# LED.net
KiCad netlist of a schematic drawn in EAGLE
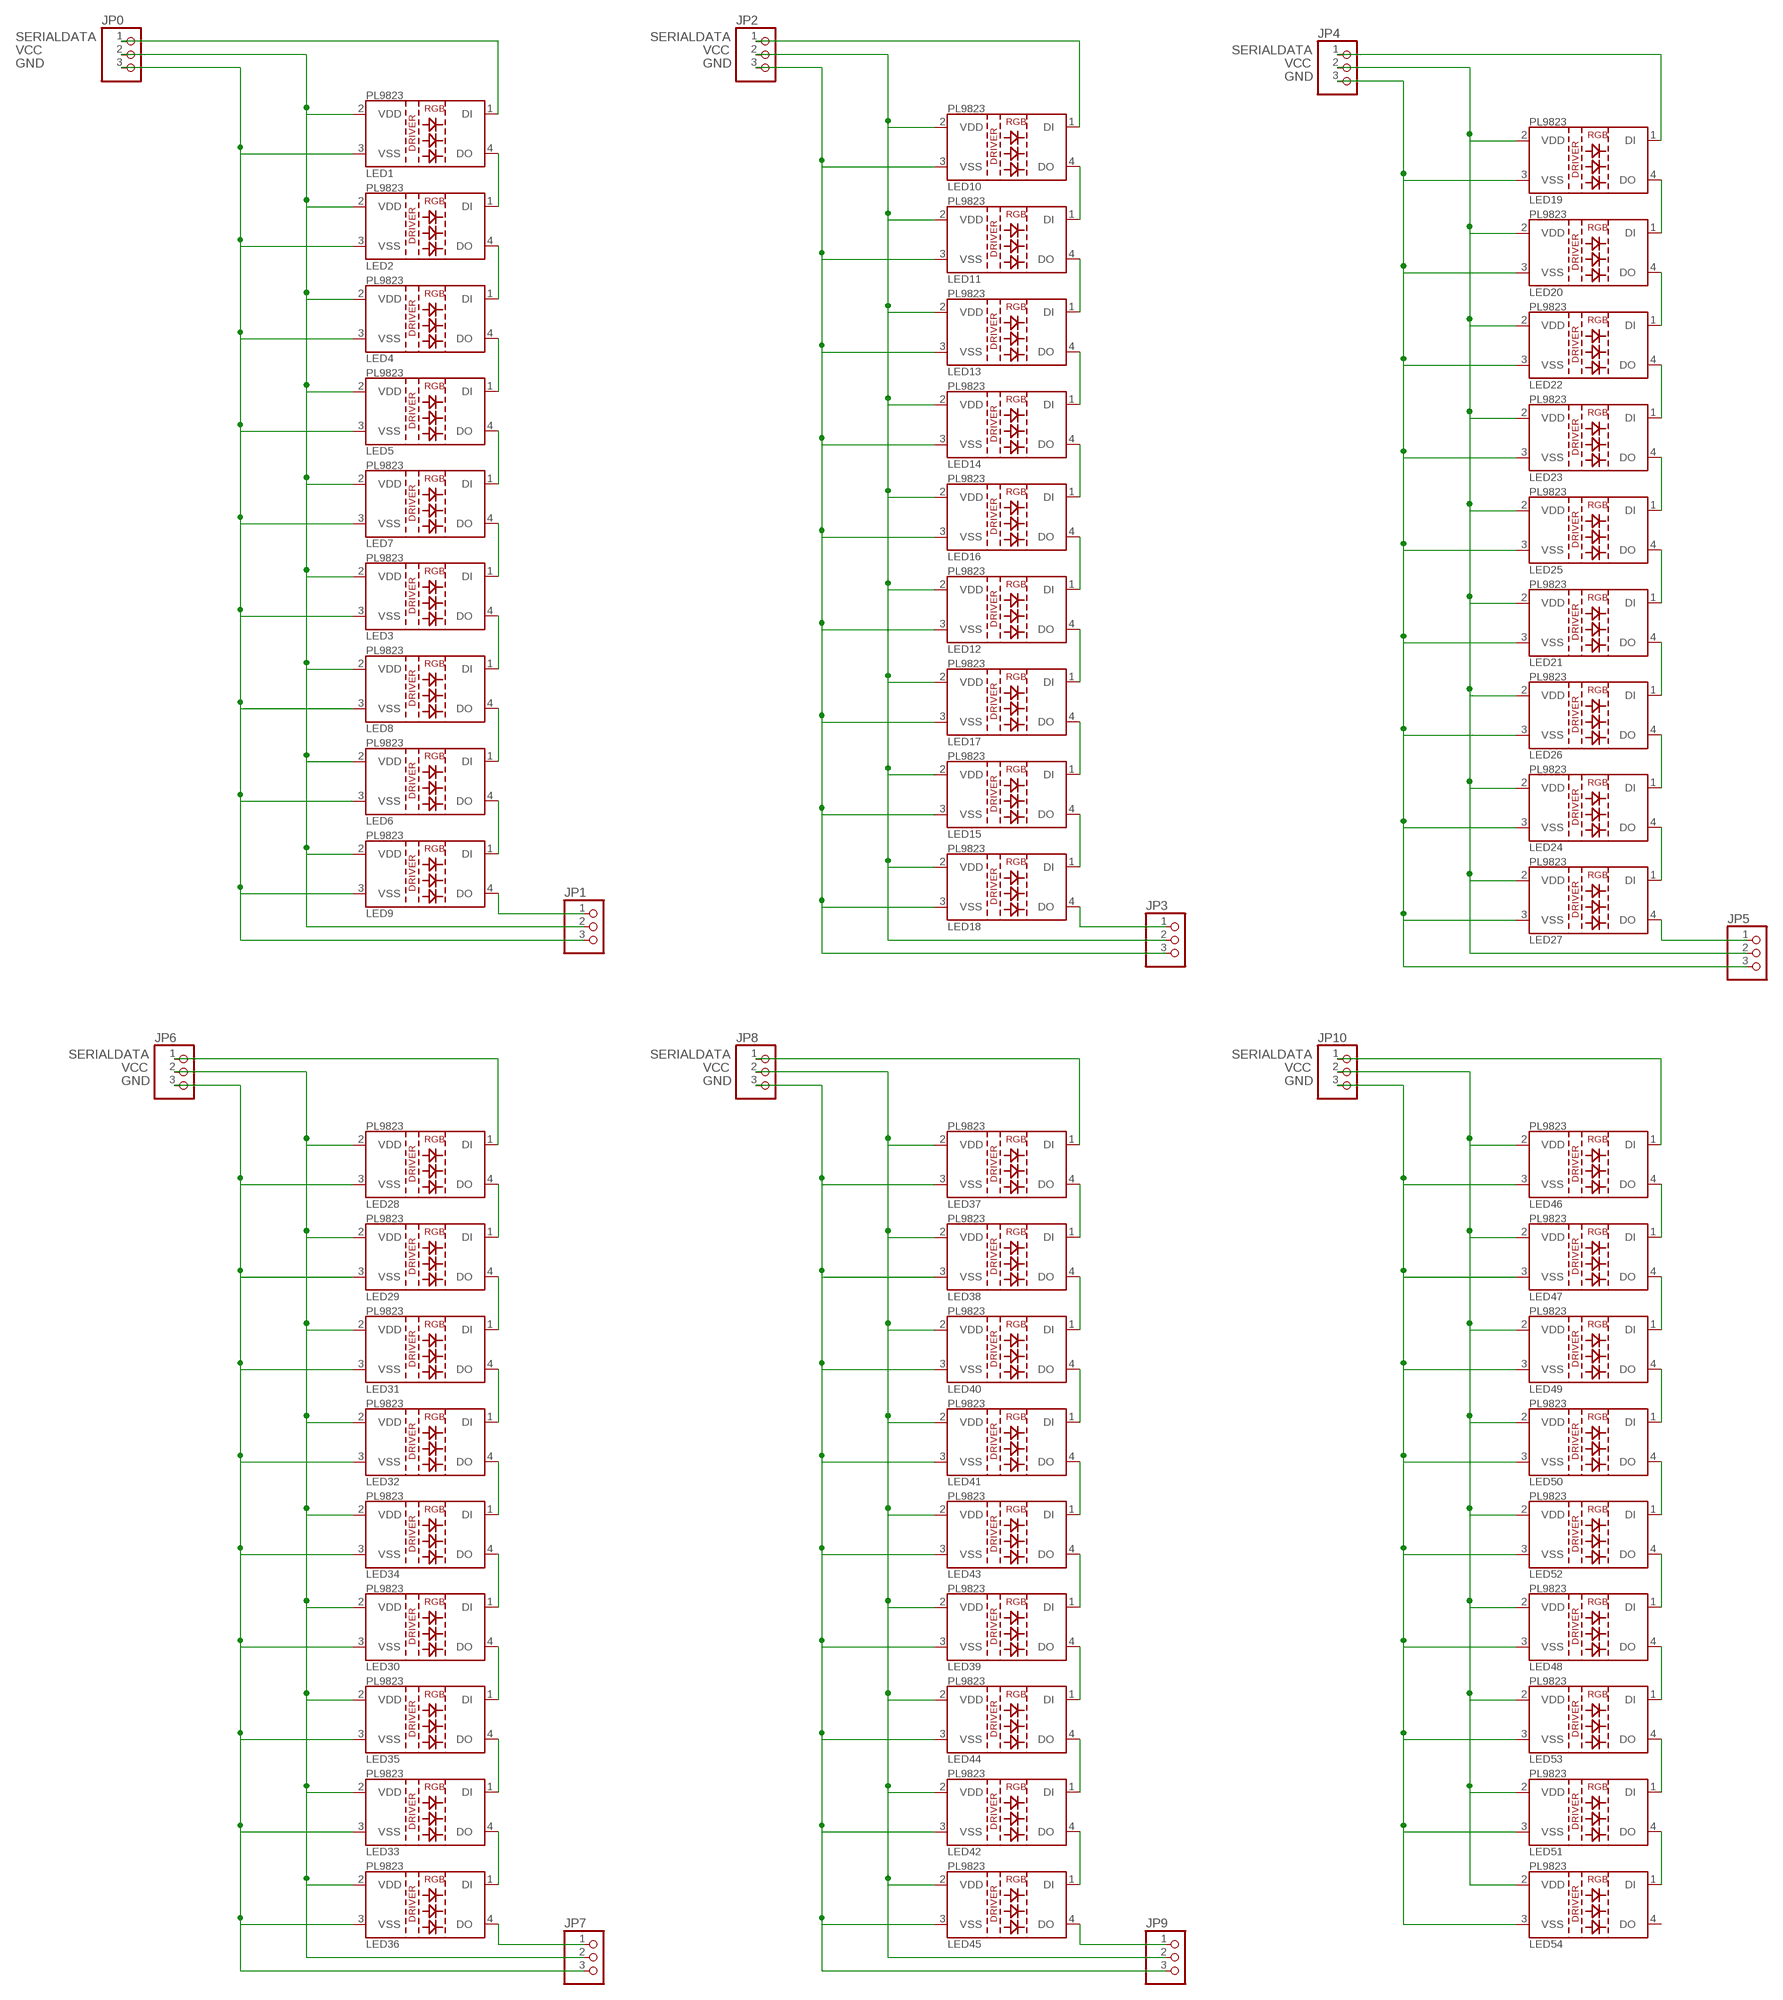
[diagram p0: schematic, sheet 1]

(export (version "E")
  (design (tool "Eeschema 10.0.6"))
  (components
    (comp (ref "JP0")
      (value "PINHD-1X3")
      (footprint "eagle-import:1X03")
      (libsource (lib "eagle-import") (part "PINHD-1X3"))
    )
    (comp (ref "JP1")
      (value "PINHD-1X3")
      (footprint "eagle-import:1X03")
      (libsource (lib "eagle-import") (part "PINHD-1X3"))
    )
    (comp (ref "JP2")
      (value "PINHD-1X3")
      (footprint "eagle-import:1X03")
      (libsource (lib "eagle-import") (part "PINHD-1X3"))
    )
    (comp (ref "JP3")
      (value "PINHD-1X3")
      (footprint "eagle-import:1X03")
      (libsource (lib "eagle-import") (part "PINHD-1X3"))
    )
    (comp (ref "JP4")
      (value "PINHD-1X3")
      (footprint "eagle-import:1X03")
      (libsource (lib "eagle-import") (part "PINHD-1X3"))
    )
    (comp (ref "JP5")
      (value "PINHD-1X3")
      (footprint "eagle-import:1X03")
      (libsource (lib "eagle-import") (part "PINHD-1X3"))
    )
    (comp (ref "JP6")
      (value "PINHD-1X3")
      (footprint "eagle-import:1X03")
      (libsource (lib "eagle-import") (part "PINHD-1X3"))
    )
    (comp (ref "JP7")
      (value "PINHD-1X3")
      (footprint "eagle-import:1X03")
      (libsource (lib "eagle-import") (part "PINHD-1X3"))
    )
    (comp (ref "JP8")
      (value "PINHD-1X3")
      (footprint "eagle-import:1X03")
      (libsource (lib "eagle-import") (part "PINHD-1X3"))
    )
    (comp (ref "JP9")
      (value "PINHD-1X3")
      (footprint "eagle-import:1X03")
      (libsource (lib "eagle-import") (part "PINHD-1X3"))
    )
    (comp (ref "JP10")
      (value "PINHD-1X3")
      (footprint "eagle-import:1X03")
      (libsource (lib "eagle-import") (part "PINHD-1X3"))
    )
    (comp (ref "LED1")
      (value "LED-PL9823-F5")
      (footprint "eagle-import:LED-PL9823-F5")
      (libsource (lib "eagle-import") (part "LED-PL9823-F5"))
    )
    (comp (ref "LED2")
      (value "LED-PL9823-F5")
      (footprint "eagle-import:LED-PL9823-F5")
      (libsource (lib "eagle-import") (part "LED-PL9823-F5"))
    )
    (comp (ref "LED3")
      (value "LED-PL9823-F5")
      (footprint "eagle-import:LED-PL9823-F5")
      (libsource (lib "eagle-import") (part "LED-PL9823-F5"))
    )
    (comp (ref "LED4")
      (value "LED-PL9823-F5")
      (footprint "eagle-import:LED-PL9823-F5")
      (libsource (lib "eagle-import") (part "LED-PL9823-F5"))
    )
    (comp (ref "LED5")
      (value "LED-PL9823-F5")
      (footprint "eagle-import:LED-PL9823-F5")
      (libsource (lib "eagle-import") (part "LED-PL9823-F5"))
    )
    (comp (ref "LED6")
      (value "LED-PL9823-F5")
      (footprint "eagle-import:LED-PL9823-F5")
      (libsource (lib "eagle-import") (part "LED-PL9823-F5"))
    )
    (comp (ref "LED7")
      (value "LED-PL9823-F5")
      (footprint "eagle-import:LED-PL9823-F5")
      (libsource (lib "eagle-import") (part "LED-PL9823-F5"))
    )
    (comp (ref "LED8")
      (value "LED-PL9823-F5")
      (footprint "eagle-import:LED-PL9823-F5")
      (libsource (lib "eagle-import") (part "LED-PL9823-F5"))
    )
    (comp (ref "LED9")
      (value "LED-PL9823-F5")
      (footprint "eagle-import:LED-PL9823-F5")
      (libsource (lib "eagle-import") (part "LED-PL9823-F5"))
    )
    (comp (ref "LED10")
      (value "LED-PL9823-F5")
      (footprint "eagle-import:LED-PL9823-F5")
      (libsource (lib "eagle-import") (part "LED-PL9823-F5"))
    )
    (comp (ref "LED11")
      (value "LED-PL9823-F5")
      (footprint "eagle-import:LED-PL9823-F5")
      (libsource (lib "eagle-import") (part "LED-PL9823-F5"))
    )
    (comp (ref "LED12")
      (value "LED-PL9823-F5")
      (footprint "eagle-import:LED-PL9823-F5")
      (libsource (lib "eagle-import") (part "LED-PL9823-F5"))
    )
    (comp (ref "LED13")
      (value "LED-PL9823-F5")
      (footprint "eagle-import:LED-PL9823-F5")
      (libsource (lib "eagle-import") (part "LED-PL9823-F5"))
    )
    (comp (ref "LED14")
      (value "LED-PL9823-F5")
      (footprint "eagle-import:LED-PL9823-F5")
      (libsource (lib "eagle-import") (part "LED-PL9823-F5"))
    )
    (comp (ref "LED15")
      (value "LED-PL9823-F5")
      (footprint "eagle-import:LED-PL9823-F5")
      (libsource (lib "eagle-import") (part "LED-PL9823-F5"))
    )
    (comp (ref "LED16")
      (value "LED-PL9823-F5")
      (footprint "eagle-import:LED-PL9823-F5")
      (libsource (lib "eagle-import") (part "LED-PL9823-F5"))
    )
    (comp (ref "LED17")
      (value "LED-PL9823-F5")
      (footprint "eagle-import:LED-PL9823-F5")
      (libsource (lib "eagle-import") (part "LED-PL9823-F5"))
    )
    (comp (ref "LED18")
      (value "LED-PL9823-F5")
      (footprint "eagle-import:LED-PL9823-F5")
      (libsource (lib "eagle-import") (part "LED-PL9823-F5"))
    )
    (comp (ref "LED19")
      (value "LED-PL9823-F5")
      (footprint "eagle-import:LED-PL9823-F5")
      (libsource (lib "eagle-import") (part "LED-PL9823-F5"))
    )
    (comp (ref "LED20")
      (value "LED-PL9823-F5")
      (footprint "eagle-import:LED-PL9823-F5")
      (libsource (lib "eagle-import") (part "LED-PL9823-F5"))
    )
    (comp (ref "LED21")
      (value "LED-PL9823-F5")
      (footprint "eagle-import:LED-PL9823-F5")
      (libsource (lib "eagle-import") (part "LED-PL9823-F5"))
    )
    (comp (ref "LED22")
      (value "LED-PL9823-F5")
      (footprint "eagle-import:LED-PL9823-F5")
      (libsource (lib "eagle-import") (part "LED-PL9823-F5"))
    )
    (comp (ref "LED23")
      (value "LED-PL9823-F5")
      (footprint "eagle-import:LED-PL9823-F5")
      (libsource (lib "eagle-import") (part "LED-PL9823-F5"))
    )
    (comp (ref "LED24")
      (value "LED-PL9823-F5")
      (footprint "eagle-import:LED-PL9823-F5")
      (libsource (lib "eagle-import") (part "LED-PL9823-F5"))
    )
    (comp (ref "LED25")
      (value "LED-PL9823-F5")
      (footprint "eagle-import:LED-PL9823-F5")
      (libsource (lib "eagle-import") (part "LED-PL9823-F5"))
    )
    (comp (ref "LED26")
      (value "LED-PL9823-F5")
      (footprint "eagle-import:LED-PL9823-F5")
      (libsource (lib "eagle-import") (part "LED-PL9823-F5"))
    )
    (comp (ref "LED27")
      (value "LED-PL9823-F5")
      (footprint "eagle-import:LED-PL9823-F5")
      (libsource (lib "eagle-import") (part "LED-PL9823-F5"))
    )
    (comp (ref "LED28")
      (value "LED-PL9823-F5")
      (footprint "eagle-import:LED-PL9823-F5")
      (libsource (lib "eagle-import") (part "LED-PL9823-F5"))
    )
    (comp (ref "LED29")
      (value "LED-PL9823-F5")
      (footprint "eagle-import:LED-PL9823-F5")
      (libsource (lib "eagle-import") (part "LED-PL9823-F5"))
    )
    (comp (ref "LED30")
      (value "LED-PL9823-F5")
      (footprint "eagle-import:LED-PL9823-F5")
      (libsource (lib "eagle-import") (part "LED-PL9823-F5"))
    )
    (comp (ref "LED31")
      (value "LED-PL9823-F5")
      (footprint "eagle-import:LED-PL9823-F5")
      (libsource (lib "eagle-import") (part "LED-PL9823-F5"))
    )
    (comp (ref "LED32")
      (value "LED-PL9823-F5")
      (footprint "eagle-import:LED-PL9823-F5")
      (libsource (lib "eagle-import") (part "LED-PL9823-F5"))
    )
    (comp (ref "LED33")
      (value "LED-PL9823-F5")
      (footprint "eagle-import:LED-PL9823-F5")
      (libsource (lib "eagle-import") (part "LED-PL9823-F5"))
    )
    (comp (ref "LED34")
      (value "LED-PL9823-F5")
      (footprint "eagle-import:LED-PL9823-F5")
      (libsource (lib "eagle-import") (part "LED-PL9823-F5"))
    )
    (comp (ref "LED35")
      (value "LED-PL9823-F5")
      (footprint "eagle-import:LED-PL9823-F5")
      (libsource (lib "eagle-import") (part "LED-PL9823-F5"))
    )
    (comp (ref "LED36")
      (value "LED-PL9823-F5")
      (footprint "eagle-import:LED-PL9823-F5")
      (libsource (lib "eagle-import") (part "LED-PL9823-F5"))
    )
    (comp (ref "LED37")
      (value "LED-PL9823-F5")
      (footprint "eagle-import:LED-PL9823-F5")
      (libsource (lib "eagle-import") (part "LED-PL9823-F5"))
    )
    (comp (ref "LED38")
      (value "LED-PL9823-F5")
      (footprint "eagle-import:LED-PL9823-F5")
      (libsource (lib "eagle-import") (part "LED-PL9823-F5"))
    )
    (comp (ref "LED39")
      (value "LED-PL9823-F5")
      (footprint "eagle-import:LED-PL9823-F5")
      (libsource (lib "eagle-import") (part "LED-PL9823-F5"))
    )
    (comp (ref "LED40")
      (value "LED-PL9823-F5")
      (footprint "eagle-import:LED-PL9823-F5")
      (libsource (lib "eagle-import") (part "LED-PL9823-F5"))
    )
    (comp (ref "LED41")
      (value "LED-PL9823-F5")
      (footprint "eagle-import:LED-PL9823-F5")
      (libsource (lib "eagle-import") (part "LED-PL9823-F5"))
    )
    (comp (ref "LED42")
      (value "LED-PL9823-F5")
      (footprint "eagle-import:LED-PL9823-F5")
      (libsource (lib "eagle-import") (part "LED-PL9823-F5"))
    )
    (comp (ref "LED43")
      (value "LED-PL9823-F5")
      (footprint "eagle-import:LED-PL9823-F5")
      (libsource (lib "eagle-import") (part "LED-PL9823-F5"))
    )
    (comp (ref "LED44")
      (value "LED-PL9823-F5")
      (footprint "eagle-import:LED-PL9823-F5")
      (libsource (lib "eagle-import") (part "LED-PL9823-F5"))
    )
    (comp (ref "LED45")
      (value "LED-PL9823-F5")
      (footprint "eagle-import:LED-PL9823-F5")
      (libsource (lib "eagle-import") (part "LED-PL9823-F5"))
    )
    (comp (ref "LED46")
      (value "LED-PL9823-F5")
      (footprint "eagle-import:LED-PL9823-F5")
      (libsource (lib "eagle-import") (part "LED-PL9823-F5"))
    )
    (comp (ref "LED47")
      (value "LED-PL9823-F5")
      (footprint "eagle-import:LED-PL9823-F5")
      (libsource (lib "eagle-import") (part "LED-PL9823-F5"))
    )
    (comp (ref "LED48")
      (value "LED-PL9823-F5")
      (footprint "eagle-import:LED-PL9823-F5")
      (libsource (lib "eagle-import") (part "LED-PL9823-F5"))
    )
    (comp (ref "LED49")
      (value "LED-PL9823-F5")
      (footprint "eagle-import:LED-PL9823-F5")
      (libsource (lib "eagle-import") (part "LED-PL9823-F5"))
    )
    (comp (ref "LED50")
      (value "LED-PL9823-F5")
      (footprint "eagle-import:LED-PL9823-F5")
      (libsource (lib "eagle-import") (part "LED-PL9823-F5"))
    )
    (comp (ref "LED51")
      (value "LED-PL9823-F5")
      (footprint "eagle-import:LED-PL9823-F5")
      (libsource (lib "eagle-import") (part "LED-PL9823-F5"))
    )
    (comp (ref "LED52")
      (value "LED-PL9823-F5")
      (footprint "eagle-import:LED-PL9823-F5")
      (libsource (lib "eagle-import") (part "LED-PL9823-F5"))
    )
    (comp (ref "LED53")
      (value "LED-PL9823-F5")
      (footprint "eagle-import:LED-PL9823-F5")
      (libsource (lib "eagle-import") (part "LED-PL9823-F5"))
    )
    (comp (ref "LED54")
      (value "LED-PL9823-F5")
      (footprint "eagle-import:LED-PL9823-F5")
      (libsource (lib "eagle-import") (part "LED-PL9823-F5"))
    )
  )
  (nets
    (net (code "1") (name "/GND") (class "Default")
      (node (ref "JP0") (pin "3") (pinfunction "3_3") (pintype "passive"))
      (node (ref "JP1") (pin "3") (pinfunction "3_3") (pintype "passive"))
      (node (ref "JP10") (pin "3") (pinfunction "3_3") (pintype "passive"))
      (node (ref "JP2") (pin "3") (pinfunction "3_3") (pintype "passive"))
      (node (ref "JP3") (pin "3") (pinfunction "3_3") (pintype "passive"))
      (node (ref "JP4") (pin "3") (pinfunction "3_3") (pintype "passive"))
      (node (ref "JP5") (pin "3") (pinfunction "3_3") (pintype "passive"))
      (node (ref "JP6") (pin "3") (pinfunction "3_3") (pintype "passive"))
      (node (ref "JP7") (pin "3") (pinfunction "3_3") (pintype "passive"))
      (node (ref "JP8") (pin "3") (pinfunction "3_3") (pintype "passive"))
      (node (ref "JP9") (pin "3") (pinfunction "3_3") (pintype "passive"))
      (node (ref "LED1") (pin "3") (pinfunction "VSS_3") (pintype "bidirectional"))
      (node (ref "LED10") (pin "3") (pinfunction "VSS_3") (pintype "bidirectional"))
      (node (ref "LED11") (pin "3") (pinfunction "VSS_3") (pintype "bidirectional"))
      (node (ref "LED12") (pin "3") (pinfunction "VSS_3") (pintype "bidirectional"))
      (node (ref "LED13") (pin "3") (pinfunction "VSS_3") (pintype "bidirectional"))
      (node (ref "LED14") (pin "3") (pinfunction "VSS_3") (pintype "bidirectional"))
      (node (ref "LED15") (pin "3") (pinfunction "VSS_3") (pintype "bidirectional"))
      (node (ref "LED16") (pin "3") (pinfunction "VSS_3") (pintype "bidirectional"))
      (node (ref "LED17") (pin "3") (pinfunction "VSS_3") (pintype "bidirectional"))
      (node (ref "LED18") (pin "3") (pinfunction "VSS_3") (pintype "bidirectional"))
      (node (ref "LED19") (pin "3") (pinfunction "VSS_3") (pintype "bidirectional"))
      (node (ref "LED2") (pin "3") (pinfunction "VSS_3") (pintype "bidirectional"))
      (node (ref "LED20") (pin "3") (pinfunction "VSS_3") (pintype "bidirectional"))
      (node (ref "LED21") (pin "3") (pinfunction "VSS_3") (pintype "bidirectional"))
      (node (ref "LED22") (pin "3") (pinfunction "VSS_3") (pintype "bidirectional"))
      (node (ref "LED23") (pin "3") (pinfunction "VSS_3") (pintype "bidirectional"))
      (node (ref "LED24") (pin "3") (pinfunction "VSS_3") (pintype "bidirectional"))
      (node (ref "LED25") (pin "3") (pinfunction "VSS_3") (pintype "bidirectional"))
      (node (ref "LED26") (pin "3") (pinfunction "VSS_3") (pintype "bidirectional"))
      (node (ref "LED27") (pin "3") (pinfunction "VSS_3") (pintype "bidirectional"))
      (node (ref "LED28") (pin "3") (pinfunction "VSS_3") (pintype "bidirectional"))
      (node (ref "LED29") (pin "3") (pinfunction "VSS_3") (pintype "bidirectional"))
      (node (ref "LED3") (pin "3") (pinfunction "VSS_3") (pintype "bidirectional"))
      (node (ref "LED30") (pin "3") (pinfunction "VSS_3") (pintype "bidirectional"))
      (node (ref "LED31") (pin "3") (pinfunction "VSS_3") (pintype "bidirectional"))
      (node (ref "LED32") (pin "3") (pinfunction "VSS_3") (pintype "bidirectional"))
      (node (ref "LED33") (pin "3") (pinfunction "VSS_3") (pintype "bidirectional"))
      (node (ref "LED34") (pin "3") (pinfunction "VSS_3") (pintype "bidirectional"))
      (node (ref "LED35") (pin "3") (pinfunction "VSS_3") (pintype "bidirectional"))
      (node (ref "LED36") (pin "3") (pinfunction "VSS_3") (pintype "bidirectional"))
      (node (ref "LED37") (pin "3") (pinfunction "VSS_3") (pintype "bidirectional"))
      (node (ref "LED38") (pin "3") (pinfunction "VSS_3") (pintype "bidirectional"))
      (node (ref "LED39") (pin "3") (pinfunction "VSS_3") (pintype "bidirectional"))
      (node (ref "LED4") (pin "3") (pinfunction "VSS_3") (pintype "bidirectional"))
      (node (ref "LED40") (pin "3") (pinfunction "VSS_3") (pintype "bidirectional"))
      (node (ref "LED41") (pin "3") (pinfunction "VSS_3") (pintype "bidirectional"))
      (node (ref "LED42") (pin "3") (pinfunction "VSS_3") (pintype "bidirectional"))
      (node (ref "LED43") (pin "3") (pinfunction "VSS_3") (pintype "bidirectional"))
      (node (ref "LED44") (pin "3") (pinfunction "VSS_3") (pintype "bidirectional"))
      (node (ref "LED45") (pin "3") (pinfunction "VSS_3") (pintype "bidirectional"))
      (node (ref "LED46") (pin "3") (pinfunction "VSS_3") (pintype "bidirectional"))
      (node (ref "LED47") (pin "3") (pinfunction "VSS_3") (pintype "bidirectional"))
      (node (ref "LED48") (pin "3") (pinfunction "VSS_3") (pintype "bidirectional"))
      (node (ref "LED49") (pin "3") (pinfunction "VSS_3") (pintype "bidirectional"))
      (node (ref "LED5") (pin "3") (pinfunction "VSS_3") (pintype "bidirectional"))
      (node (ref "LED50") (pin "3") (pinfunction "VSS_3") (pintype "bidirectional"))
      (node (ref "LED51") (pin "3") (pinfunction "VSS_3") (pintype "bidirectional"))
      (node (ref "LED52") (pin "3") (pinfunction "VSS_3") (pintype "bidirectional"))
      (node (ref "LED53") (pin "3") (pinfunction "VSS_3") (pintype "bidirectional"))
      (node (ref "LED54") (pin "3") (pinfunction "VSS_3") (pintype "bidirectional"))
      (node (ref "LED6") (pin "3") (pinfunction "VSS_3") (pintype "bidirectional"))
      (node (ref "LED7") (pin "3") (pinfunction "VSS_3") (pintype "bidirectional"))
      (node (ref "LED8") (pin "3") (pinfunction "VSS_3") (pintype "bidirectional"))
      (node (ref "LED9") (pin "3") (pinfunction "VSS_3") (pintype "bidirectional"))
    )
    (net (code "2") (name "/SERIALDATA") (class "Default")
      (node (ref "JP0") (pin "1") (pinfunction "1_1") (pintype "passive"))
      (node (ref "JP10") (pin "1") (pinfunction "1_1") (pintype "passive"))
      (node (ref "JP2") (pin "1") (pinfunction "1_1") (pintype "passive"))
      (node (ref "JP4") (pin "1") (pinfunction "1_1") (pintype "passive"))
      (node (ref "JP6") (pin "1") (pinfunction "1_1") (pintype "passive"))
      (node (ref "JP8") (pin "1") (pinfunction "1_1") (pintype "passive"))
      (node (ref "LED1") (pin "1") (pinfunction "DI_1") (pintype "bidirectional"))
      (node (ref "LED10") (pin "1") (pinfunction "DI_1") (pintype "bidirectional"))
      (node (ref "LED19") (pin "1") (pinfunction "DI_1") (pintype "bidirectional"))
      (node (ref "LED28") (pin "1") (pinfunction "DI_1") (pintype "bidirectional"))
      (node (ref "LED37") (pin "1") (pinfunction "DI_1") (pintype "bidirectional"))
      (node (ref "LED46") (pin "1") (pinfunction "DI_1") (pintype "bidirectional"))
    )
    (net (code "3") (name "/VCC") (class "Default")
      (node (ref "JP0") (pin "2") (pinfunction "2_2") (pintype "passive"))
      (node (ref "JP1") (pin "2") (pinfunction "2_2") (pintype "passive"))
      (node (ref "JP10") (pin "2") (pinfunction "2_2") (pintype "passive"))
      (node (ref "JP2") (pin "2") (pinfunction "2_2") (pintype "passive"))
      (node (ref "JP3") (pin "2") (pinfunction "2_2") (pintype "passive"))
      (node (ref "JP4") (pin "2") (pinfunction "2_2") (pintype "passive"))
      (node (ref "JP5") (pin "2") (pinfunction "2_2") (pintype "passive"))
      (node (ref "JP6") (pin "2") (pinfunction "2_2") (pintype "passive"))
      (node (ref "JP7") (pin "2") (pinfunction "2_2") (pintype "passive"))
      (node (ref "JP8") (pin "2") (pinfunction "2_2") (pintype "passive"))
      (node (ref "JP9") (pin "2") (pinfunction "2_2") (pintype "passive"))
      (node (ref "LED1") (pin "2") (pinfunction "VDD_2") (pintype "bidirectional"))
      (node (ref "LED10") (pin "2") (pinfunction "VDD_2") (pintype "bidirectional"))
      (node (ref "LED11") (pin "2") (pinfunction "VDD_2") (pintype "bidirectional"))
      (node (ref "LED12") (pin "2") (pinfunction "VDD_2") (pintype "bidirectional"))
      (node (ref "LED13") (pin "2") (pinfunction "VDD_2") (pintype "bidirectional"))
      (node (ref "LED14") (pin "2") (pinfunction "VDD_2") (pintype "bidirectional"))
      (node (ref "LED15") (pin "2") (pinfunction "VDD_2") (pintype "bidirectional"))
      (node (ref "LED16") (pin "2") (pinfunction "VDD_2") (pintype "bidirectional"))
      (node (ref "LED17") (pin "2") (pinfunction "VDD_2") (pintype "bidirectional"))
      (node (ref "LED18") (pin "2") (pinfunction "VDD_2") (pintype "bidirectional"))
      (node (ref "LED19") (pin "2") (pinfunction "VDD_2") (pintype "bidirectional"))
      (node (ref "LED2") (pin "2") (pinfunction "VDD_2") (pintype "bidirectional"))
      (node (ref "LED20") (pin "2") (pinfunction "VDD_2") (pintype "bidirectional"))
      (node (ref "LED21") (pin "2") (pinfunction "VDD_2") (pintype "bidirectional"))
      (node (ref "LED22") (pin "2") (pinfunction "VDD_2") (pintype "bidirectional"))
      (node (ref "LED23") (pin "2") (pinfunction "VDD_2") (pintype "bidirectional"))
      (node (ref "LED24") (pin "2") (pinfunction "VDD_2") (pintype "bidirectional"))
      (node (ref "LED25") (pin "2") (pinfunction "VDD_2") (pintype "bidirectional"))
      (node (ref "LED26") (pin "2") (pinfunction "VDD_2") (pintype "bidirectional"))
      (node (ref "LED27") (pin "2") (pinfunction "VDD_2") (pintype "bidirectional"))
      (node (ref "LED28") (pin "2") (pinfunction "VDD_2") (pintype "bidirectional"))
      (node (ref "LED29") (pin "2") (pinfunction "VDD_2") (pintype "bidirectional"))
      (node (ref "LED3") (pin "2") (pinfunction "VDD_2") (pintype "bidirectional"))
      (node (ref "LED30") (pin "2") (pinfunction "VDD_2") (pintype "bidirectional"))
      (node (ref "LED31") (pin "2") (pinfunction "VDD_2") (pintype "bidirectional"))
      (node (ref "LED32") (pin "2") (pinfunction "VDD_2") (pintype "bidirectional"))
      (node (ref "LED33") (pin "2") (pinfunction "VDD_2") (pintype "bidirectional"))
      (node (ref "LED34") (pin "2") (pinfunction "VDD_2") (pintype "bidirectional"))
      (node (ref "LED35") (pin "2") (pinfunction "VDD_2") (pintype "bidirectional"))
      (node (ref "LED36") (pin "2") (pinfunction "VDD_2") (pintype "bidirectional"))
      (node (ref "LED37") (pin "2") (pinfunction "VDD_2") (pintype "bidirectional"))
      (node (ref "LED38") (pin "2") (pinfunction "VDD_2") (pintype "bidirectional"))
      (node (ref "LED39") (pin "2") (pinfunction "VDD_2") (pintype "bidirectional"))
      (node (ref "LED4") (pin "2") (pinfunction "VDD_2") (pintype "bidirectional"))
      (node (ref "LED40") (pin "2") (pinfunction "VDD_2") (pintype "bidirectional"))
      (node (ref "LED41") (pin "2") (pinfunction "VDD_2") (pintype "bidirectional"))
      (node (ref "LED42") (pin "2") (pinfunction "VDD_2") (pintype "bidirectional"))
      (node (ref "LED43") (pin "2") (pinfunction "VDD_2") (pintype "bidirectional"))
      (node (ref "LED44") (pin "2") (pinfunction "VDD_2") (pintype "bidirectional"))
      (node (ref "LED45") (pin "2") (pinfunction "VDD_2") (pintype "bidirectional"))
      (node (ref "LED46") (pin "2") (pinfunction "VDD_2") (pintype "bidirectional"))
      (node (ref "LED47") (pin "2") (pinfunction "VDD_2") (pintype "bidirectional"))
      (node (ref "LED48") (pin "2") (pinfunction "VDD_2") (pintype "bidirectional"))
      (node (ref "LED49") (pin "2") (pinfunction "VDD_2") (pintype "bidirectional"))
      (node (ref "LED5") (pin "2") (pinfunction "VDD_2") (pintype "bidirectional"))
      (node (ref "LED50") (pin "2") (pinfunction "VDD_2") (pintype "bidirectional"))
      (node (ref "LED51") (pin "2") (pinfunction "VDD_2") (pintype "bidirectional"))
      (node (ref "LED52") (pin "2") (pinfunction "VDD_2") (pintype "bidirectional"))
      (node (ref "LED53") (pin "2") (pinfunction "VDD_2") (pintype "bidirectional"))
      (node (ref "LED54") (pin "2") (pinfunction "VDD_2") (pintype "bidirectional"))
      (node (ref "LED6") (pin "2") (pinfunction "VDD_2") (pintype "bidirectional"))
      (node (ref "LED7") (pin "2") (pinfunction "VDD_2") (pintype "bidirectional"))
      (node (ref "LED8") (pin "2") (pinfunction "VDD_2") (pintype "bidirectional"))
      (node (ref "LED9") (pin "2") (pinfunction "VDD_2") (pintype "bidirectional"))
    )
    (net (code "4") (name "Net-(LED1-DO)") (class "Default")
      (node (ref "LED1") (pin "4") (pinfunction "DO_4") (pintype "bidirectional"))
      (node (ref "LED2") (pin "1") (pinfunction "DI_1") (pintype "bidirectional"))
    )
    (net (code "5") (name "Net-(LED2-DO)") (class "Default")
      (node (ref "LED2") (pin "4") (pinfunction "DO_4") (pintype "bidirectional"))
      (node (ref "LED4") (pin "1") (pinfunction "DI_1") (pintype "bidirectional"))
    )
    (net (code "6") (name "Net-(LED3-DI)") (class "Default")
      (node (ref "LED3") (pin "1") (pinfunction "DI_1") (pintype "bidirectional"))
      (node (ref "LED7") (pin "4") (pinfunction "DO_4") (pintype "bidirectional"))
    )
    (net (code "7") (name "Net-(LED3-DO)") (class "Default")
      (node (ref "LED3") (pin "4") (pinfunction "DO_4") (pintype "bidirectional"))
      (node (ref "LED8") (pin "1") (pinfunction "DI_1") (pintype "bidirectional"))
    )
    (net (code "8") (name "Net-(LED4-DO)") (class "Default")
      (node (ref "LED4") (pin "4") (pinfunction "DO_4") (pintype "bidirectional"))
      (node (ref "LED5") (pin "1") (pinfunction "DI_1") (pintype "bidirectional"))
    )
    (net (code "9") (name "Net-(LED5-DO)") (class "Default")
      (node (ref "LED5") (pin "4") (pinfunction "DO_4") (pintype "bidirectional"))
      (node (ref "LED7") (pin "1") (pinfunction "DI_1") (pintype "bidirectional"))
    )
    (net (code "10") (name "Net-(LED6-DI)") (class "Default")
      (node (ref "LED6") (pin "1") (pinfunction "DI_1") (pintype "bidirectional"))
      (node (ref "LED8") (pin "4") (pinfunction "DO_4") (pintype "bidirectional"))
    )
    (net (code "11") (name "Net-(LED6-DO)") (class "Default")
      (node (ref "LED6") (pin "4") (pinfunction "DO_4") (pintype "bidirectional"))
      (node (ref "LED9") (pin "1") (pinfunction "DI_1") (pintype "bidirectional"))
    )
    (net (code "12") (name "Net-(LED9-DO)") (class "Default")
      (node (ref "JP1") (pin "1") (pinfunction "1_1") (pintype "passive"))
      (node (ref "LED9") (pin "4") (pinfunction "DO_4") (pintype "bidirectional"))
    )
    (net (code "13") (name "Net-(LED10-DO)") (class "Default")
      (node (ref "LED10") (pin "4") (pinfunction "DO_4") (pintype "bidirectional"))
      (node (ref "LED11") (pin "1") (pinfunction "DI_1") (pintype "bidirectional"))
    )
    (net (code "14") (name "Net-(LED11-DO)") (class "Default")
      (node (ref "LED11") (pin "4") (pinfunction "DO_4") (pintype "bidirectional"))
      (node (ref "LED13") (pin "1") (pinfunction "DI_1") (pintype "bidirectional"))
    )
    (net (code "15") (name "Net-(LED12-DI)") (class "Default")
      (node (ref "LED12") (pin "1") (pinfunction "DI_1") (pintype "bidirectional"))
      (node (ref "LED16") (pin "4") (pinfunction "DO_4") (pintype "bidirectional"))
    )
    (net (code "16") (name "Net-(LED12-DO)") (class "Default")
      (node (ref "LED12") (pin "4") (pinfunction "DO_4") (pintype "bidirectional"))
      (node (ref "LED17") (pin "1") (pinfunction "DI_1") (pintype "bidirectional"))
    )
    (net (code "17") (name "Net-(LED13-DO)") (class "Default")
      (node (ref "LED13") (pin "4") (pinfunction "DO_4") (pintype "bidirectional"))
      (node (ref "LED14") (pin "1") (pinfunction "DI_1") (pintype "bidirectional"))
    )
    (net (code "18") (name "Net-(LED14-DO)") (class "Default")
      (node (ref "LED14") (pin "4") (pinfunction "DO_4") (pintype "bidirectional"))
      (node (ref "LED16") (pin "1") (pinfunction "DI_1") (pintype "bidirectional"))
    )
    (net (code "19") (name "Net-(LED15-DI)") (class "Default")
      (node (ref "LED15") (pin "1") (pinfunction "DI_1") (pintype "bidirectional"))
      (node (ref "LED17") (pin "4") (pinfunction "DO_4") (pintype "bidirectional"))
    )
    (net (code "20") (name "Net-(LED15-DO)") (class "Default")
      (node (ref "LED15") (pin "4") (pinfunction "DO_4") (pintype "bidirectional"))
      (node (ref "LED18") (pin "1") (pinfunction "DI_1") (pintype "bidirectional"))
    )
    (net (code "21") (name "Net-(LED18-DO)") (class "Default")
      (node (ref "JP3") (pin "1") (pinfunction "1_1") (pintype "passive"))
      (node (ref "LED18") (pin "4") (pinfunction "DO_4") (pintype "bidirectional"))
    )
    (net (code "22") (name "Net-(LED19-DO)") (class "Default")
      (node (ref "LED19") (pin "4") (pinfunction "DO_4") (pintype "bidirectional"))
      (node (ref "LED20") (pin "1") (pinfunction "DI_1") (pintype "bidirectional"))
    )
    (net (code "23") (name "Net-(LED20-DO)") (class "Default")
      (node (ref "LED20") (pin "4") (pinfunction "DO_4") (pintype "bidirectional"))
      (node (ref "LED22") (pin "1") (pinfunction "DI_1") (pintype "bidirectional"))
    )
    (net (code "24") (name "Net-(LED21-DI)") (class "Default")
      (node (ref "LED21") (pin "1") (pinfunction "DI_1") (pintype "bidirectional"))
      (node (ref "LED25") (pin "4") (pinfunction "DO_4") (pintype "bidirectional"))
    )
    (net (code "25") (name "Net-(LED21-DO)") (class "Default")
      (node (ref "LED21") (pin "4") (pinfunction "DO_4") (pintype "bidirectional"))
      (node (ref "LED26") (pin "1") (pinfunction "DI_1") (pintype "bidirectional"))
    )
    (net (code "26") (name "Net-(LED22-DO)") (class "Default")
      (node (ref "LED22") (pin "4") (pinfunction "DO_4") (pintype "bidirectional"))
      (node (ref "LED23") (pin "1") (pinfunction "DI_1") (pintype "bidirectional"))
    )
    (net (code "27") (name "Net-(LED23-DO)") (class "Default")
      (node (ref "LED23") (pin "4") (pinfunction "DO_4") (pintype "bidirectional"))
      (node (ref "LED25") (pin "1") (pinfunction "DI_1") (pintype "bidirectional"))
    )
    (net (code "28") (name "Net-(LED24-DI)") (class "Default")
      (node (ref "LED24") (pin "1") (pinfunction "DI_1") (pintype "bidirectional"))
      (node (ref "LED26") (pin "4") (pinfunction "DO_4") (pintype "bidirectional"))
    )
    (net (code "29") (name "Net-(LED24-DO)") (class "Default")
      (node (ref "LED24") (pin "4") (pinfunction "DO_4") (pintype "bidirectional"))
      (node (ref "LED27") (pin "1") (pinfunction "DI_1") (pintype "bidirectional"))
    )
    (net (code "30") (name "Net-(LED27-DO)") (class "Default")
      (node (ref "JP5") (pin "1") (pinfunction "1_1") (pintype "passive"))
      (node (ref "LED27") (pin "4") (pinfunction "DO_4") (pintype "bidirectional"))
    )
    (net (code "31") (name "Net-(LED28-DO)") (class "Default")
      (node (ref "LED28") (pin "4") (pinfunction "DO_4") (pintype "bidirectional"))
      (node (ref "LED29") (pin "1") (pinfunction "DI_1") (pintype "bidirectional"))
    )
    (net (code "32") (name "Net-(LED29-DO)") (class "Default")
      (node (ref "LED29") (pin "4") (pinfunction "DO_4") (pintype "bidirectional"))
      (node (ref "LED31") (pin "1") (pinfunction "DI_1") (pintype "bidirectional"))
    )
    (net (code "33") (name "Net-(LED30-DI)") (class "Default")
      (node (ref "LED30") (pin "1") (pinfunction "DI_1") (pintype "bidirectional"))
      (node (ref "LED34") (pin "4") (pinfunction "DO_4") (pintype "bidirectional"))
    )
    (net (code "34") (name "Net-(LED30-DO)") (class "Default")
      (node (ref "LED30") (pin "4") (pinfunction "DO_4") (pintype "bidirectional"))
      (node (ref "LED35") (pin "1") (pinfunction "DI_1") (pintype "bidirectional"))
    )
    (net (code "35") (name "Net-(LED31-DO)") (class "Default")
      (node (ref "LED31") (pin "4") (pinfunction "DO_4") (pintype "bidirectional"))
      (node (ref "LED32") (pin "1") (pinfunction "DI_1") (pintype "bidirectional"))
    )
    (net (code "36") (name "Net-(LED32-DO)") (class "Default")
      (node (ref "LED32") (pin "4") (pinfunction "DO_4") (pintype "bidirectional"))
      (node (ref "LED34") (pin "1") (pinfunction "DI_1") (pintype "bidirectional"))
    )
    (net (code "37") (name "Net-(LED33-DI)") (class "Default")
      (node (ref "LED33") (pin "1") (pinfunction "DI_1") (pintype "bidirectional"))
      (node (ref "LED35") (pin "4") (pinfunction "DO_4") (pintype "bidirectional"))
    )
    (net (code "38") (name "Net-(LED33-DO)") (class "Default")
      (node (ref "LED33") (pin "4") (pinfunction "DO_4") (pintype "bidirectional"))
      (node (ref "LED36") (pin "1") (pinfunction "DI_1") (pintype "bidirectional"))
    )
    (net (code "39") (name "Net-(LED36-DO)") (class "Default")
      (node (ref "JP7") (pin "1") (pinfunction "1_1") (pintype "passive"))
      (node (ref "LED36") (pin "4") (pinfunction "DO_4") (pintype "bidirectional"))
    )
    (net (code "40") (name "Net-(LED37-DO)") (class "Default")
      (node (ref "LED37") (pin "4") (pinfunction "DO_4") (pintype "bidirectional"))
      (node (ref "LED38") (pin "1") (pinfunction "DI_1") (pintype "bidirectional"))
    )
    (net (code "41") (name "Net-(LED38-DO)") (class "Default")
      (node (ref "LED38") (pin "4") (pinfunction "DO_4") (pintype "bidirectional"))
      (node (ref "LED40") (pin "1") (pinfunction "DI_1") (pintype "bidirectional"))
    )
    (net (code "42") (name "Net-(LED39-DI)") (class "Default")
      (node (ref "LED39") (pin "1") (pinfunction "DI_1") (pintype "bidirectional"))
      (node (ref "LED43") (pin "4") (pinfunction "DO_4") (pintype "bidirectional"))
    )
    (net (code "43") (name "Net-(LED39-DO)") (class "Default")
      (node (ref "LED39") (pin "4") (pinfunction "DO_4") (pintype "bidirectional"))
      (node (ref "LED44") (pin "1") (pinfunction "DI_1") (pintype "bidirectional"))
    )
    (net (code "44") (name "Net-(LED40-DO)") (class "Default")
      (node (ref "LED40") (pin "4") (pinfunction "DO_4") (pintype "bidirectional"))
      (node (ref "LED41") (pin "1") (pinfunction "DI_1") (pintype "bidirectional"))
    )
    (net (code "45") (name "Net-(LED41-DO)") (class "Default")
      (node (ref "LED41") (pin "4") (pinfunction "DO_4") (pintype "bidirectional"))
      (node (ref "LED43") (pin "1") (pinfunction "DI_1") (pintype "bidirectional"))
    )
    (net (code "46") (name "Net-(LED42-DI)") (class "Default")
      (node (ref "LED42") (pin "1") (pinfunction "DI_1") (pintype "bidirectional"))
      (node (ref "LED44") (pin "4") (pinfunction "DO_4") (pintype "bidirectional"))
    )
    (net (code "47") (name "Net-(LED42-DO)") (class "Default")
      (node (ref "LED42") (pin "4") (pinfunction "DO_4") (pintype "bidirectional"))
      (node (ref "LED45") (pin "1") (pinfunction "DI_1") (pintype "bidirectional"))
    )
    (net (code "48") (name "Net-(LED45-DO)") (class "Default")
      (node (ref "JP9") (pin "1") (pinfunction "1_1") (pintype "passive"))
      (node (ref "LED45") (pin "4") (pinfunction "DO_4") (pintype "bidirectional"))
    )
    (net (code "49") (name "Net-(LED46-DO)") (class "Default")
      (node (ref "LED46") (pin "4") (pinfunction "DO_4") (pintype "bidirectional"))
      (node (ref "LED47") (pin "1") (pinfunction "DI_1") (pintype "bidirectional"))
    )
    (net (code "50") (name "Net-(LED47-DO)") (class "Default")
      (node (ref "LED47") (pin "4") (pinfunction "DO_4") (pintype "bidirectional"))
      (node (ref "LED49") (pin "1") (pinfunction "DI_1") (pintype "bidirectional"))
    )
    (net (code "51") (name "Net-(LED48-DI)") (class "Default")
      (node (ref "LED48") (pin "1") (pinfunction "DI_1") (pintype "bidirectional"))
      (node (ref "LED52") (pin "4") (pinfunction "DO_4") (pintype "bidirectional"))
    )
    (net (code "52") (name "Net-(LED48-DO)") (class "Default")
      (node (ref "LED48") (pin "4") (pinfunction "DO_4") (pintype "bidirectional"))
      (node (ref "LED53") (pin "1") (pinfunction "DI_1") (pintype "bidirectional"))
    )
    (net (code "53") (name "Net-(LED49-DO)") (class "Default")
      (node (ref "LED49") (pin "4") (pinfunction "DO_4") (pintype "bidirectional"))
      (node (ref "LED50") (pin "1") (pinfunction "DI_1") (pintype "bidirectional"))
    )
    (net (code "54") (name "Net-(LED50-DO)") (class "Default")
      (node (ref "LED50") (pin "4") (pinfunction "DO_4") (pintype "bidirectional"))
      (node (ref "LED52") (pin "1") (pinfunction "DI_1") (pintype "bidirectional"))
    )
    (net (code "55") (name "Net-(LED51-DI)") (class "Default")
      (node (ref "LED51") (pin "1") (pinfunction "DI_1") (pintype "bidirectional"))
      (node (ref "LED53") (pin "4") (pinfunction "DO_4") (pintype "bidirectional"))
    )
    (net (code "56") (name "Net-(LED51-DO)") (class "Default")
      (node (ref "LED51") (pin "4") (pinfunction "DO_4") (pintype "bidirectional"))
      (node (ref "LED54") (pin "1") (pinfunction "DI_1") (pintype "bidirectional"))
    )
    (net (code "57") (name "unconnected-(LED54-DO-Pad4)") (class "Default")
      (node (ref "LED54") (pin "4") (pinfunction "DO_4") (pintype "bidirectional"))
    )
  )
)
